# pic_k42.net
KiCad netlist of a schematic drawn in EAGLE
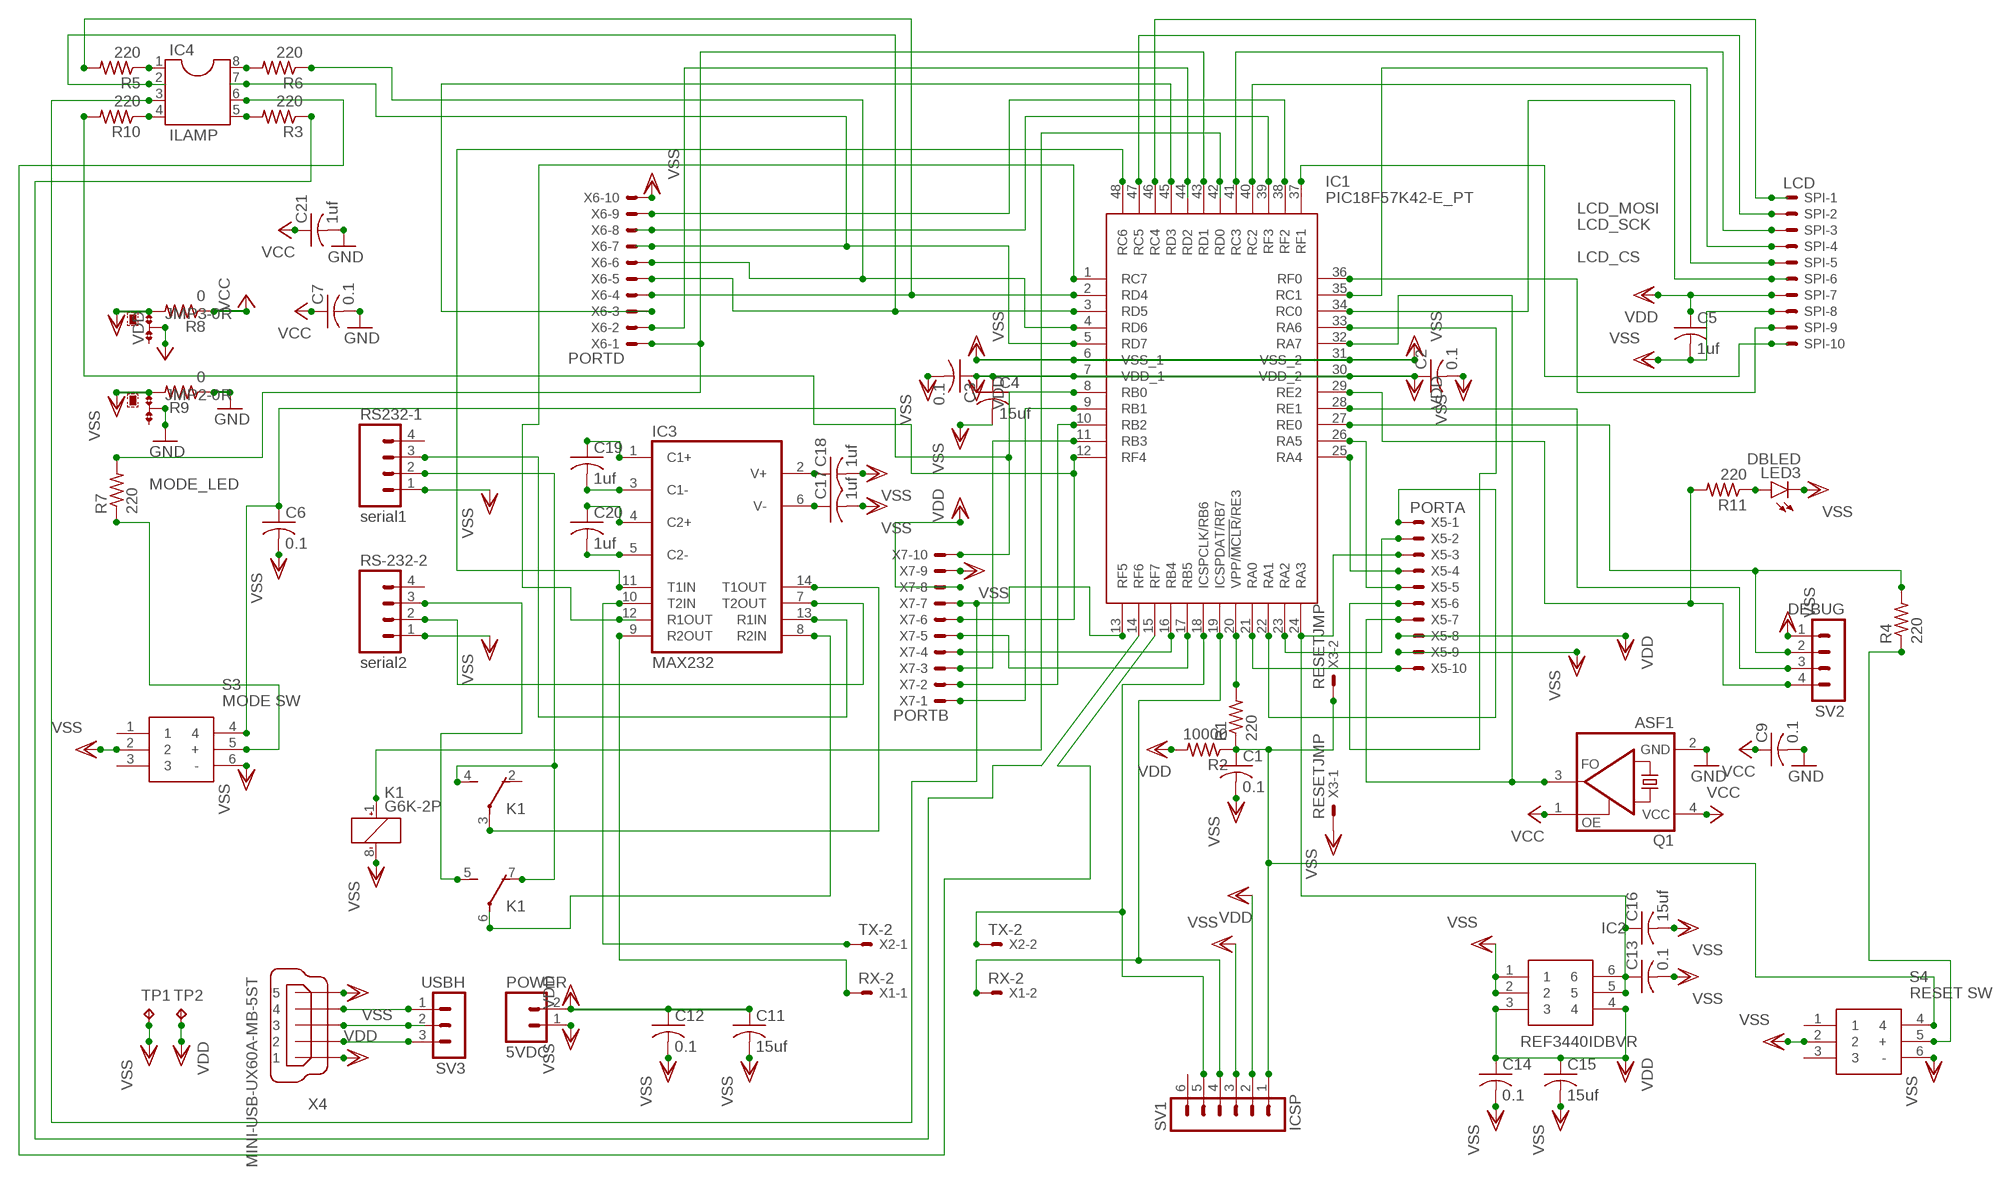
[diagram p0: schematic, sheet 1]

(export (version "E")
  (design (tool "Eeschema 10.0.6"))
  (components
    (comp (ref "C1")
      (value "0.1")
      (footprint "eagle-import:C1206")
      (libsource (lib "eagle-import") (part "C-USC1206"))
    )
    (comp (ref "C2")
      (value "0.1")
      (footprint "eagle-import:C1206")
      (libsource (lib "eagle-import") (part "C-USC1206"))
    )
    (comp (ref "C3")
      (value "0.1")
      (footprint "eagle-import:C1206")
      (libsource (lib "eagle-import") (part "C-USC1206"))
    )
    (comp (ref "C4")
      (value "15uf")
      (footprint "eagle-import:C1206")
      (libsource (lib "eagle-import") (part "C-USC1206"))
    )
    (comp (ref "C5")
      (value "1uf")
      (footprint "eagle-import:C0805")
      (libsource (lib "eagle-import") (part "C-USC0805"))
    )
    (comp (ref "C6")
      (value "0.1")
      (footprint "eagle-import:C1206")
      (libsource (lib "eagle-import") (part "C-USC1206"))
    )
    (comp (ref "C7")
      (value "0.1")
      (footprint "eagle-import:C1206")
      (libsource (lib "eagle-import") (part "C-USC1206"))
    )
    (comp (ref "C9")
      (value "0.1")
      (footprint "eagle-import:C1206")
      (libsource (lib "eagle-import") (part "C-USC1206"))
    )
    (comp (ref "C11")
      (value "15uf")
      (footprint "eagle-import:C1206")
      (libsource (lib "eagle-import") (part "C-USC1206"))
    )
    (comp (ref "C12")
      (value "0.1")
      (footprint "eagle-import:C1206")
      (libsource (lib "eagle-import") (part "C-USC1206"))
    )
    (comp (ref "C13")
      (value "0.1")
      (footprint "eagle-import:C1206")
      (libsource (lib "eagle-import") (part "C-USC1206"))
    )
    (comp (ref "C14")
      (value "0.1")
      (footprint "eagle-import:C1206")
      (libsource (lib "eagle-import") (part "C-USC1206"))
    )
    (comp (ref "C15")
      (value "15uf")
      (footprint "eagle-import:C1206")
      (libsource (lib "eagle-import") (part "C-USC1206"))
    )
    (comp (ref "C16")
      (value "15uf")
      (footprint "eagle-import:C1206")
      (libsource (lib "eagle-import") (part "C-USC1206"))
    )
    (comp (ref "C17")
      (value "1uf")
      (footprint "eagle-import:C0805")
      (libsource (lib "eagle-import") (part "C-USC0805"))
    )
    (comp (ref "C18")
      (value "1uf")
      (footprint "eagle-import:C0805")
      (libsource (lib "eagle-import") (part "C-USC0805"))
    )
    (comp (ref "C19")
      (value "1uf")
      (footprint "eagle-import:C0805")
      (libsource (lib "eagle-import") (part "C-USC0805"))
    )
    (comp (ref "C20")
      (value "1uf")
      (footprint "eagle-import:C0805")
      (libsource (lib "eagle-import") (part "C-USC0805"))
    )
    (comp (ref "C21")
      (value "1uf")
      (footprint "eagle-import:C0805")
      (libsource (lib "eagle-import") (part "C-USC0805"))
    )
    (comp (ref "IC1")
      (value "PIC18F57K42-E_PT")
      (footprint "eagle-import:QFP50P900X900X120-48N")
      (fields
        (field (name "MANUFACTURER_PART_NUMBER") "PIC18F57K42-E/PT")
        (field (name "MOUSER_PART_NUMBER") "579-PIC18F57K42-E/PT")
      )
      (libsource (lib "eagle-import") (part "PIC18F57K42-E_PT"))
    )
    (comp (ref "IC2")
      (value "REF3440IDBVR")
      (footprint "eagle-import:SOP95P280X145-6N")
      (libsource (lib "eagle-import") (part "REF3440IDBVR"))
    )
    (comp (ref "IC3")
      (value "MAX232")
      (footprint "eagle-import:DIL16")
      (fields (field (name "MF") "MAXIM") (field (name "MPN") "MAX232ACPE+"))
      (libsource (lib "eagle-import") (part "MAX232"))
    )
    (comp (ref "IC4")
      (value "ILAMP")
      (footprint "eagle-import:SOCKET-08")
      (libsource (lib "eagle-import") (part "DIL8S"))
    )
    (comp (ref "JMP2")
      (value "0R-JUMPA")
      (footprint "eagle-import:A0R-JMP")
      (libsource (lib "eagle-import") (part "0R-JUMPA"))
    )
    (comp (ref "JMP3")
      (value "0R-JUMPA")
      (footprint "eagle-import:A0R-JMP")
      (libsource (lib "eagle-import") (part "0R-JUMPA"))
    )
    (comp (ref "K1")
      (value "G6K-2P")
      (footprint "eagle-import:G6K-2P")
      (fields (field (name "MF") "OMRON COMPONENTS USA") (field (name "MPN") "G6K-2P DC3"))
      (libsource (lib "eagle-import") (part "G6K-2P"))
    )
    (comp (ref "LED3")
      (value "DBLED")
      (footprint "eagle-import:CHIPLED_1206")
      (libsource (lib "eagle-import") (part "LEDCHIPLED_1206"))
    )
    (comp (ref "POWER")
      (value "5VDC")
      (footprint "eagle-import:02P")
      (libsource (lib "eagle-import") (part "M02"))
    )
    (comp (ref "Q1")
      (value "ASF1")
      (footprint "eagle-import:ASF")
      (libsource (lib "eagle-import") (part "ASF1"))
    )
    (comp (ref "R1")
      (value "220")
      (footprint "eagle-import:R1206")
      (libsource (lib "eagle-import") (part "R-US_R1206"))
    )
    (comp (ref "R2")
      (value "10000")
      (footprint "eagle-import:R1206")
      (libsource (lib "eagle-import") (part "R-US_R1206"))
    )
    (comp (ref "R3")
      (value "220")
      (footprint "eagle-import:R1206")
      (libsource (lib "eagle-import") (part "R-US_R1206"))
    )
    (comp (ref "R4")
      (value "220")
      (footprint "eagle-import:R1206")
      (libsource (lib "eagle-import") (part "R-US_R1206"))
    )
    (comp (ref "R5")
      (value "220")
      (footprint "eagle-import:R1206")
      (libsource (lib "eagle-import") (part "R-US_R1206"))
    )
    (comp (ref "R6")
      (value "220")
      (footprint "eagle-import:R1206")
      (libsource (lib "eagle-import") (part "R-US_R1206"))
    )
    (comp (ref "R7")
      (value "220")
      (footprint "eagle-import:R1206")
      (libsource (lib "eagle-import") (part "R-US_R1206"))
    )
    (comp (ref "R8")
      (value "0")
      (footprint "eagle-import:R1206")
      (libsource (lib "eagle-import") (part "R-US_R1206"))
    )
    (comp (ref "R9")
      (value "0")
      (footprint "eagle-import:R1206")
      (libsource (lib "eagle-import") (part "R-US_R1206"))
    )
    (comp (ref "R10")
      (value "220")
      (footprint "eagle-import:R1206")
      (libsource (lib "eagle-import") (part "R-US_R1206"))
    )
    (comp (ref "R11")
      (value "220")
      (footprint "eagle-import:R1206")
      (libsource (lib "eagle-import") (part "R-US_R1206"))
    )
    (comp (ref "RS-232-2")
      (value "serial2")
      (footprint "eagle-import:04P")
      (libsource (lib "eagle-import") (part "M04"))
    )
    (comp (ref "RS232-1")
      (value "serial1")
      (footprint "eagle-import:04P")
      (libsource (lib "eagle-import") (part "M04"))
    )
    (comp (ref "S3")
      (value "MODE SW")
      (footprint "eagle-import:B3W-9_1-LED")
      (fields
        (field (name "MANUFACTURER_PART_NUMBER") "B3W-9000-Y1N")
        (field (name "MOUSER_PART_NUMBER") "653-B3W-9000-Y1N")
        (field (name "RS_PART_NUMBER") "0492777P")
      )
      (libsource (lib "eagle-import") (part "B3W-9000-Y1N"))
    )
    (comp (ref "S4")
      (value "RESET SW")
      (footprint "eagle-import:B3W-9_1-LED")
      (fields
        (field (name "MANUFACTURER_PART_NUMBER") "B3W-9000-Y1N")
        (field (name "MOUSER_PART_NUMBER") "653-B3W-9000-Y1N")
        (field (name "RS_PART_NUMBER") "0492777P")
      )
      (libsource (lib "eagle-import") (part "B3W-9000-Y1N"))
    )
    (comp (ref "SPI")
      (value "LCD")
      (footprint "eagle-import:22-23-2101")
      (fields (field (name "MF") "MOLEX") (field (name "MPN") "22-23-2101"))
      (libsource (lib "eagle-import") (part "22-23-2101"))
    )
    (comp (ref "SV1")
      (value "ICSP")
      (footprint "eagle-import:MA06-1")
      (libsource (lib "eagle-import") (part "MA06-1"))
    )
    (comp (ref "SV2")
      (value "DEBUG")
      (footprint "eagle-import:MA04-1")
      (libsource (lib "eagle-import") (part "MA04-1"))
    )
    (comp (ref "SV3")
      (value "USBH")
      (footprint "eagle-import:MA03-1")
      (libsource (lib "eagle-import") (part "MA03-1"))
    )
    (comp (ref "TP1")
      (value "TPB1,27")
      (footprint "eagle-import:B1,27")
      (libsource (lib "eagle-import") (part "TPB1,27"))
    )
    (comp (ref "TP2")
      (value "TPB1,27")
      (footprint "eagle-import:B1,27")
      (libsource (lib "eagle-import") (part "TPB1,27"))
    )
    (comp (ref "X1")
      (value "RX-2")
      (footprint "eagle-import:332-02")
      (libsource (lib "eagle-import") (part "332-02"))
    )
    (comp (ref "X2")
      (value "TX-2")
      (footprint "eagle-import:332-02")
      (libsource (lib "eagle-import") (part "332-02"))
    )
    (comp (ref "X3")
      (value "RESETJMP")
      (footprint "eagle-import:332-02")
      (libsource (lib "eagle-import") (part "332-02"))
    )
    (comp (ref "X4")
      (value "MINI-USB-UX60A-MB-5ST")
      (footprint "eagle-import:UX60A-MB-5ST")
      (libsource (lib "eagle-import") (part "MINI-USB-UX60A-MB-5ST"))
    )
    (comp (ref "X5")
      (value "PORTA")
      (footprint "eagle-import:22-23-2101")
      (fields (field (name "MF") "MOLEX") (field (name "MPN") "22-23-2101"))
      (libsource (lib "eagle-import") (part "22-23-2101"))
    )
    (comp (ref "X6")
      (value "PORTD")
      (footprint "eagle-import:22-23-2101")
      (fields (field (name "MF") "MOLEX") (field (name "MPN") "22-23-2101"))
      (libsource (lib "eagle-import") (part "22-23-2101"))
    )
    (comp (ref "X7")
      (value "PORTB")
      (footprint "eagle-import:22-23-2101")
      (fields (field (name "MF") "MOLEX") (field (name "MPN") "22-23-2101"))
      (libsource (lib "eagle-import") (part "22-23-2101"))
    )
  )
  (nets
    (net (code "1") (name "/LCD_CS") (class "Default")
      (node (ref "IC1") (pin "40") (pinfunction "RC2_40") (pintype "bidirectional"))
      (node (ref "SPI") (pin "5") (pinfunction "S_5") (pintype "passive"))
    )
    (net (code "2") (name "/LCD_MOSI") (class "Default")
      (node (ref "IC1") (pin "47") (pinfunction "RC5_47") (pintype "bidirectional"))
      (node (ref "SPI") (pin "2") (pinfunction "S_2") (pintype "passive"))
    )
    (net (code "3") (name "/LCD_SCK") (class "Default")
      (node (ref "IC1") (pin "41") (pinfunction "RC3_41") (pintype "bidirectional"))
      (node (ref "SPI") (pin "3") (pinfunction "S_3") (pintype "passive"))
    )
    (net (code "4") (name "/MODE_LED") (class "Default")
      (node (ref "IC1") (pin "43") (pinfunction "RD1_43") (pintype "bidirectional"))
      (node (ref "R7") (pin "2") (pinfunction "2_2") (pintype "passive"))
      (node (ref "X6") (pin "1") (pinfunction "S_1") (pintype "passive"))
    )
    (net (code "5") (name "GND") (class "Default")
      (node (ref "C21") (pin "2") (pinfunction "2_2") (pintype "passive"))
      (node (ref "C7") (pin "2") (pinfunction "2_2") (pintype "passive"))
      (node (ref "C9") (pin "2") (pinfunction "2_2") (pintype "passive"))
      (node (ref "JMP2") (pin "2") (pinfunction "2_2") (pintype "passive"))
      (node (ref "Q1") (pin "2") (pinfunction "GND_2") (pintype "power_in"))
      (node (ref "R9") (pin "1") (pinfunction "1_1") (pintype "passive"))
    )
    (net (code "6") (name "Net-(IC1-ICSPCLK{slash}RB6)") (class "Default")
      (node (ref "IC1") (pin "18") (pinfunction "ICSPCLK/RB6_18") (pintype "bidirectional"))
      (node (ref "SV1") (pin "5") (pinfunction "5_5") (pintype "passive"))
      (node (ref "X2") (pin "2") (pinfunction "S_2") (pintype "passive"))
    )
    (net (code "7") (name "Net-(IC1-ICSPDAT{slash}RB7)") (class "Default")
      (node (ref "IC1") (pin "19") (pinfunction "ICSPDAT/RB7_19") (pintype "bidirectional"))
      (node (ref "SV1") (pin "4") (pinfunction "4_4") (pintype "passive"))
      (node (ref "X1") (pin "2") (pinfunction "S_2") (pintype "passive"))
    )
    (net (code "8") (name "Net-(IC1-RA0)") (class "Default")
      (node (ref "IC1") (pin "21") (pinfunction "RA0_21") (pintype "bidirectional"))
      (node (ref "X5") (pin "10") (pinfunction "S_10") (pintype "passive"))
    )
    (net (code "9") (name "Net-(IC1-RA1)") (class "Default")
      (node (ref "IC1") (pin "22") (pinfunction "RA1_22") (pintype "bidirectional"))
      (node (ref "X5") (pin "1") (pinfunction "S_1") (pintype "passive"))
    )
    (net (code "10") (name "Net-(IC1-RA2)") (class "Default")
      (node (ref "IC1") (pin "23") (pinfunction "RA2_23") (pintype "bidirectional"))
      (node (ref "X5") (pin "2") (pinfunction "S_2") (pintype "passive"))
    )
    (net (code "11") (name "Net-(IC1-RA3)") (class "Default")
      (node (ref "C13") (pin "1") (pinfunction "1_1") (pintype "passive"))
      (node (ref "C16") (pin "1") (pinfunction "1_1") (pintype "passive"))
      (node (ref "IC1") (pin "24") (pinfunction "RA3_24") (pintype "bidirectional"))
      (node (ref "IC2") (pin "5") (pinfunction "5_5") (pintype "bidirectional"))
      (node (ref "IC2") (pin "6") (pinfunction "6_6") (pintype "bidirectional"))
      (node (ref "X5") (pin "3") (pinfunction "S_3") (pintype "passive"))
    )
    (net (code "12") (name "Net-(IC1-RA4)") (class "Default")
      (node (ref "IC1") (pin "25") (pinfunction "RA4_25") (pintype "bidirectional"))
      (node (ref "X5") (pin "4") (pinfunction "S_4") (pintype "passive"))
    )
    (net (code "13") (name "Net-(IC1-RA5)") (class "Default")
      (node (ref "IC1") (pin "26") (pinfunction "RA5_26") (pintype "bidirectional"))
      (node (ref "X5") (pin "5") (pinfunction "S_5") (pintype "passive"))
    )
    (net (code "14") (name "Net-(IC1-RA6)") (class "Default")
      (node (ref "IC1") (pin "33") (pinfunction "RA6_33") (pintype "bidirectional"))
      (node (ref "X5") (pin "6") (pinfunction "S_6") (pintype "passive"))
    )
    (net (code "15") (name "Net-(IC1-RA7)") (class "Default")
      (node (ref "IC1") (pin "32") (pinfunction "RA7_32") (pintype "bidirectional"))
      (node (ref "Q1") (pin "3") (pinfunction "FO_3") (pintype "output"))
      (node (ref "X5") (pin "7") (pinfunction "S_7") (pintype "passive"))
    )
    (net (code "16") (name "Net-(IC1-RB0)") (class "Default")
      (node (ref "C6") (pin "1") (pinfunction "1_1") (pintype "passive"))
      (node (ref "IC1") (pin "8") (pinfunction "RB0_8") (pintype "bidirectional"))
      (node (ref "S3") (pin "4") (pinfunction "4_4") (pintype "bidirectional"))
      (node (ref "X7") (pin "10") (pinfunction "S_10") (pintype "passive"))
    )
    (net (code "17") (name "Net-(IC1-RB1)") (class "Default")
      (node (ref "IC1") (pin "9") (pinfunction "RB1_9") (pintype "bidirectional"))
      (node (ref "X7") (pin "1") (pinfunction "S_1") (pintype "passive"))
    )
    (net (code "18") (name "Net-(IC1-RB2)") (class "Default")
      (node (ref "IC1") (pin "10") (pinfunction "RB2_10") (pintype "bidirectional"))
      (node (ref "X7") (pin "2") (pinfunction "S_2") (pintype "passive"))
    )
    (net (code "19") (name "Net-(IC1-RB3)") (class "Default")
      (node (ref "IC1") (pin "11") (pinfunction "RB3_11") (pintype "bidirectional"))
      (node (ref "X7") (pin "3") (pinfunction "S_3") (pintype "passive"))
    )
    (net (code "20") (name "Net-(IC1-RB4)") (class "Default")
      (node (ref "IC1") (pin "16") (pinfunction "RB4_16") (pintype "bidirectional"))
      (node (ref "X7") (pin "4") (pinfunction "S_4") (pintype "passive"))
    )
    (net (code "21") (name "Net-(IC1-RB5)") (class "Default")
      (node (ref "IC1") (pin "17") (pinfunction "RB5_17") (pintype "bidirectional"))
      (node (ref "X7") (pin "5") (pinfunction "S_5") (pintype "passive"))
    )
    (net (code "22") (name "Net-(IC1-RC0)") (class "Default")
      (node (ref "IC1") (pin "34") (pinfunction "RC0_34") (pintype "bidirectional"))
      (node (ref "SPI") (pin "6") (pinfunction "S_6") (pintype "passive"))
    )
    (net (code "23") (name "Net-(IC1-RC1)") (class "Default")
      (node (ref "IC1") (pin "35") (pinfunction "RC1_35") (pintype "bidirectional"))
      (node (ref "SPI") (pin "4") (pinfunction "S_4") (pintype "passive"))
    )
    (net (code "24") (name "Net-(IC1-RC4)") (class "Default")
      (node (ref "IC1") (pin "46") (pinfunction "RC4_46") (pintype "bidirectional"))
      (node (ref "SPI") (pin "1") (pinfunction "S_1") (pintype "passive"))
    )
    (net (code "25") (name "Net-(IC1-RC6)") (class "Default")
      (node (ref "IC1") (pin "48") (pinfunction "RC6_48") (pintype "bidirectional"))
      (node (ref "IC3") (pin "11") (pinfunction "T1IN_11") (pintype "input"))
    )
    (net (code "26") (name "Net-(IC1-RC7)") (class "Default")
      (node (ref "IC1") (pin "1") (pinfunction "RC7_1") (pintype "bidirectional"))
      (node (ref "IC3") (pin "12") (pinfunction "R1OUT_12") (pintype "output"))
    )
    (net (code "27") (name "Net-(IC1-RD0)") (class "Default")
      (node (ref "IC1") (pin "42") (pinfunction "RD0_42") (pintype "bidirectional"))
      (node (ref "K1") (pin "1") (pinfunction "+_1") (pintype "passive"))
    )
    (net (code "28") (name "Net-(IC1-RD2)") (class "Default")
      (node (ref "IC1") (pin "44") (pinfunction "RD2_44") (pintype "bidirectional"))
      (node (ref "X6") (pin "2") (pinfunction "S_2") (pintype "passive"))
    )
    (net (code "29") (name "Net-(IC1-RD3)") (class "Default")
      (node (ref "IC1") (pin "45") (pinfunction "RD3_45") (pintype "bidirectional"))
      (node (ref "X6") (pin "3") (pinfunction "S_3") (pintype "passive"))
    )
    (net (code "30") (name "Net-(IC1-RD4)") (class "Default")
      (node (ref "IC1") (pin "2") (pinfunction "RD4_2") (pintype "bidirectional"))
      (node (ref "R5") (pin "2") (pinfunction "2_2") (pintype "passive"))
      (node (ref "X6") (pin "4") (pinfunction "S_4") (pintype "passive"))
    )
    (net (code "31") (name "Net-(IC1-RD5)") (class "Default")
      (node (ref "IC1") (pin "3") (pinfunction "RD5_3") (pintype "bidirectional"))
      (node (ref "IC4") (pin "2") (pinfunction "2_2") (pintype "passive"))
      (node (ref "X6") (pin "5") (pinfunction "S_5") (pintype "passive"))
    )
    (net (code "32") (name "Net-(IC1-RD6)") (class "Default")
      (node (ref "IC1") (pin "4") (pinfunction "RD6_4") (pintype "bidirectional"))
      (node (ref "R6") (pin "1") (pinfunction "1_1") (pintype "passive"))
      (node (ref "X6") (pin "6") (pinfunction "S_6") (pintype "passive"))
    )
    (net (code "33") (name "Net-(IC1-RD7)") (class "Default")
      (node (ref "IC1") (pin "5") (pinfunction "RD7_5") (pintype "bidirectional"))
      (node (ref "IC4") (pin "7") (pinfunction "7_7") (pintype "passive"))
      (node (ref "X6") (pin "7") (pinfunction "S_7") (pintype "passive"))
    )
    (net (code "34") (name "Net-(IC1-RE0)") (class "Default")
      (node (ref "IC1") (pin "27") (pinfunction "RE0_27") (pintype "bidirectional"))
      (node (ref "R4") (pin "2") (pinfunction "2_2") (pintype "passive"))
      (node (ref "SV2") (pin "2") (pinfunction "2_2") (pintype "passive"))
    )
    (net (code "35") (name "Net-(IC1-RE1)") (class "Default")
      (node (ref "IC1") (pin "28") (pinfunction "RE1_28") (pintype "bidirectional"))
      (node (ref "SV2") (pin "3") (pinfunction "3_3") (pintype "passive"))
    )
    (net (code "36") (name "Net-(IC1-RE2)") (class "Default")
      (node (ref "IC1") (pin "29") (pinfunction "RE2_29") (pintype "bidirectional"))
      (node (ref "R11") (pin "2") (pinfunction "2_2") (pintype "passive"))
      (node (ref "SV2") (pin "4") (pinfunction "4_4") (pintype "passive"))
    )
    (net (code "37") (name "Net-(IC1-RF0)") (class "Default")
      (node (ref "IC1") (pin "36") (pinfunction "RF0_36") (pintype "bidirectional"))
      (node (ref "SPI") (pin "9") (pinfunction "S_9") (pintype "passive"))
    )
    (net (code "38") (name "Net-(IC1-RF1)") (class "Default")
      (node (ref "IC1") (pin "37") (pinfunction "RF1_37") (pintype "bidirectional"))
      (node (ref "SPI") (pin "10") (pinfunction "S_10") (pintype "passive"))
    )
    (net (code "39") (name "Net-(IC1-RF2)") (class "Default")
      (node (ref "IC1") (pin "38") (pinfunction "RF2_38") (pintype "bidirectional"))
      (node (ref "X6") (pin "9") (pinfunction "S_9") (pintype "passive"))
    )
    (net (code "40") (name "Net-(IC1-RF3)") (class "Default")
      (node (ref "IC1") (pin "39") (pinfunction "RF3_39") (pintype "bidirectional"))
      (node (ref "X6") (pin "8") (pinfunction "S_8") (pintype "passive"))
    )
    (net (code "41") (name "Net-(IC1-RF4)") (class "Default")
      (node (ref "IC1") (pin "12") (pinfunction "RF4_12") (pintype "bidirectional"))
      (node (ref "R10") (pin "2") (pinfunction "2_2") (pintype "passive"))
      (node (ref "X7") (pin "6") (pinfunction "S_6") (pintype "passive"))
    )
    (net (code "42") (name "Net-(IC1-RF5)") (class "Default")
      (node (ref "IC1") (pin "13") (pinfunction "RF5_13") (pintype "bidirectional"))
      (node (ref "IC4") (pin "3") (pinfunction "3_3") (pintype "passive"))
      (node (ref "X7") (pin "7") (pinfunction "S_7") (pintype "passive"))
    )
    (net (code "43") (name "Net-(IC1-RF6)") (class "Default")
      (node (ref "IC1") (pin "14") (pinfunction "RF6_14") (pintype "bidirectional"))
      (node (ref "R3") (pin "1") (pinfunction "1_1") (pintype "passive"))
    )
    (net (code "44") (name "Net-(IC1-RF7)") (class "Default")
      (node (ref "IC1") (pin "15") (pinfunction "RF7_15") (pintype "bidirectional"))
      (node (ref "IC4") (pin "6") (pinfunction "6_6") (pintype "passive"))
    )
    (net (code "45") (name "Net-(IC1-VPP{slash}~{MCLR}{slash}RE3)") (class "Default")
      (node (ref "IC1") (pin "20") (pinfunction "VPP/~{MCLR}/RE3_20") (pintype "bidirectional"))
      (node (ref "R1") (pin "2") (pinfunction "2_2") (pintype "passive"))
    )
    (net (code "46") (name "Net-(IC3A-C1+)") (class "Default")
      (node (ref "C19") (pin "1") (pinfunction "1_1") (pintype "passive"))
      (node (ref "IC3") (pin "1") (pinfunction "C1+_1") (pintype "bidirectional"))
    )
    (net (code "47") (name "Net-(IC3A-C1-)") (class "Default")
      (node (ref "C19") (pin "2") (pinfunction "2_2") (pintype "passive"))
      (node (ref "IC3") (pin "3") (pinfunction "C1-_3") (pintype "bidirectional"))
    )
    (net (code "48") (name "Net-(IC3A-C2+)") (class "Default")
      (node (ref "C20") (pin "1") (pinfunction "1_1") (pintype "passive"))
      (node (ref "IC3") (pin "4") (pinfunction "C2+_4") (pintype "bidirectional"))
    )
    (net (code "49") (name "Net-(IC3A-C2-)") (class "Default")
      (node (ref "C20") (pin "2") (pinfunction "2_2") (pintype "passive"))
      (node (ref "IC3") (pin "5") (pinfunction "C2-_5") (pintype "bidirectional"))
    )
    (net (code "50") (name "Net-(IC3A-R1IN)") (class "Default")
      (node (ref "IC3") (pin "13") (pinfunction "R1IN_13") (pintype "input"))
      (node (ref "RS232-1") (pin "3") (pinfunction "3_3") (pintype "passive"))
    )
    (net (code "51") (name "Net-(IC3A-R2IN)") (class "Default")
      (node (ref "IC3") (pin "8") (pinfunction "R2IN_8") (pintype "input"))
      (node (ref "K1") (pin "6") (pinfunction "P_6") (pintype "passive"))
    )
    (net (code "52") (name "Net-(IC3A-R2OUT)") (class "Default")
      (node (ref "IC3") (pin "9") (pinfunction "R2OUT_9") (pintype "output"))
      (node (ref "X1") (pin "1") (pinfunction "S_1") (pintype "passive"))
    )
    (net (code "53") (name "Net-(IC3A-T1OUT)") (class "Default")
      (node (ref "IC3") (pin "14") (pinfunction "T1OUT_14") (pintype "output"))
      (node (ref "K1") (pin "3") (pinfunction "P_3") (pintype "passive"))
    )
    (net (code "54") (name "Net-(IC3A-T2IN)") (class "Default")
      (node (ref "IC3") (pin "10") (pinfunction "T2IN_10") (pintype "input"))
      (node (ref "X2") (pin "1") (pinfunction "S_1") (pintype "passive"))
    )
    (net (code "55") (name "Net-(IC3A-T2OUT)") (class "Default")
      (node (ref "IC3") (pin "7") (pinfunction "T2OUT_7") (pintype "output"))
      (node (ref "RS-232-2") (pin "2") (pinfunction "2_2") (pintype "passive"))
    )
    (net (code "56") (name "Net-(IC3A-V+)") (class "Default")
      (node (ref "C18") (pin "1") (pinfunction "1_1") (pintype "passive"))
      (node (ref "IC3") (pin "2") (pinfunction "V+_2") (pintype "bidirectional"))
    )
    (net (code "57") (name "Net-(IC3A-V-)") (class "Default")
      (node (ref "C17") (pin "1") (pinfunction "1_1") (pintype "passive"))
      (node (ref "IC3") (pin "6") (pinfunction "V-_6") (pintype "bidirectional"))
    )
    (net (code "58") (name "Net-(IC4-Pad1)") (class "Default")
      (node (ref "IC4") (pin "1") (pinfunction "1_1") (pintype "passive"))
      (node (ref "R5") (pin "1") (pinfunction "1_1") (pintype "passive"))
    )
    (net (code "59") (name "Net-(IC4-Pad4)") (class "Default")
      (node (ref "IC4") (pin "4") (pinfunction "4_4") (pintype "passive"))
      (node (ref "R10") (pin "1") (pinfunction "1_1") (pintype "passive"))
    )
    (net (code "60") (name "Net-(IC4-Pad5)") (class "Default")
      (node (ref "IC4") (pin "5") (pinfunction "5_5") (pintype "passive"))
      (node (ref "R3") (pin "2") (pinfunction "2_2") (pintype "passive"))
    )
    (net (code "61") (name "Net-(IC4-Pad8)") (class "Default")
      (node (ref "IC4") (pin "8") (pinfunction "8_8") (pintype "passive"))
      (node (ref "R6") (pin "2") (pinfunction "2_2") (pintype "passive"))
    )
    (net (code "62") (name "Net-(K1B-S)") (class "Default")
      (node (ref "K1") (pin "4") (pinfunction "S_4") (pintype "passive"))
      (node (ref "K1") (pin "7") (pinfunction "O_7") (pintype "passive"))
      (node (ref "RS232-1") (pin "2") (pinfunction "2_2") (pintype "passive"))
    )
    (net (code "63") (name "Net-(K1C-S)") (class "Default")
      (node (ref "K1") (pin "5") (pinfunction "S_5") (pintype "passive"))
      (node (ref "RS-232-2") (pin "3") (pinfunction "3_3") (pintype "passive"))
    )
    (net (code "64") (name "Net-(LED3-PadA)") (class "Default")
      (node (ref "LED3") (pin "A") (pinfunction "A_A") (pintype "passive"))
      (node (ref "R11") (pin "1") (pinfunction "1_1") (pintype "passive"))
    )
    (net (code "65") (name "Net-(S3-+)") (class "Default")
      (node (ref "R7") (pin "1") (pinfunction "1_1") (pintype "passive"))
      (node (ref "S3") (pin "5") (pinfunction "+_5") (pintype "bidirectional"))
    )
    (net (code "66") (name "Net-(S4-+)") (class "Default")
      (node (ref "R4") (pin "1") (pinfunction "1_1") (pintype "passive"))
      (node (ref "S4") (pin "5") (pinfunction "+_5") (pintype "bidirectional"))
    )
    (net (code "67") (name "Net-(SV3-Pad1)") (class "Default")
      (node (ref "SV3") (pin "1") (pinfunction "1_1") (pintype "passive"))
      (node (ref "X4") (pin "4") (pinfunction "4_4") (pintype "input"))
    )
    (net (code "68") (name "Net-(SV3-Pad2)") (class "Default")
      (node (ref "SV3") (pin "2") (pinfunction "2_2") (pintype "passive"))
      (node (ref "X4") (pin "3") (pinfunction "3_3") (pintype "input"))
    )
    (net (code "69") (name "Net-(SV3-Pad3)") (class "Default")
      (node (ref "SV3") (pin "3") (pinfunction "3_3") (pintype "passive"))
      (node (ref "X4") (pin "2") (pinfunction "2_2") (pintype "input"))
    )
    (net (code "70") (name "Net-(X3B-S)") (class "Default")
      (node (ref "C1") (pin "1") (pinfunction "1_1") (pintype "passive"))
      (node (ref "R1") (pin "1") (pinfunction "1_1") (pintype "passive"))
      (node (ref "R2") (pin "1") (pinfunction "1_1") (pintype "passive"))
      (node (ref "S4") (pin "4") (pinfunction "4_4") (pintype "bidirectional"))
      (node (ref "SV1") (pin "1") (pinfunction "1_1") (pintype "passive"))
      (node (ref "X3") (pin "2") (pinfunction "S_2") (pintype "passive"))
    )
    (net (code "71") (name "VCC") (class "Default")
      (node (ref "C21") (pin "1") (pinfunction "1_1") (pintype "passive"))
      (node (ref "C7") (pin "1") (pinfunction "1_1") (pintype "passive"))
      (node (ref "C9") (pin "1") (pinfunction "1_1") (pintype "passive"))
      (node (ref "JMP3") (pin "2") (pinfunction "2_2") (pintype "passive"))
      (node (ref "Q1") (pin "1") (pinfunction "OE_1") (pintype "input"))
      (node (ref "Q1") (pin "4") (pinfunction "VCC_4") (pintype "power_in"))
      (node (ref "R8") (pin "1") (pinfunction "1_1") (pintype "passive"))
    )
    (net (code "72") (name "VDD") (class "Default")
      (node (ref "C11") (pin "1") (pinfunction "1_1") (pintype "passive"))
      (node (ref "C12") (pin "1") (pinfunction "1_1") (pintype "passive"))
      (node (ref "C14") (pin "1") (pinfunction "1_1") (pintype "passive"))
      (node (ref "C15") (pin "1") (pinfunction "1_1") (pintype "passive"))
      (node (ref "C2") (pin "1") (pinfunction "1_1") (pintype "passive"))
      (node (ref "C3") (pin "1") (pinfunction "1_1") (pintype "passive"))
      (node (ref "C4") (pin "1") (pinfunction "1_1") (pintype "passive"))
      (node (ref "C5") (pin "1") (pinfunction "1_1") (pintype "passive"))
      (node (ref "IC1") (pin "30") (pinfunction "VDD_2_30") (pintype "bidirectional"))
      (node (ref "IC1") (pin "7") (pinfunction "VDD_1_7") (pintype "bidirectional"))
      (node (ref "IC2") (pin "3") (pinfunction "3_3") (pintype "bidirectional"))
      (node (ref "IC2") (pin "4") (pinfunction "4_4") (pintype "bidirectional"))
      (node (ref "JMP3") (pin "1") (pinfunction "1_1") (pintype "passive"))
      (node (ref "POWER") (pin "2") (pinfunction "2_2") (pintype "passive"))
      (node (ref "R2") (pin "2") (pinfunction "2_2") (pintype "passive"))
      (node (ref "R8") (pin "2") (pinfunction "2_2") (pintype "passive"))
      (node (ref "SPI") (pin "7") (pinfunction "S_7") (pintype "passive"))
      (node (ref "SV1") (pin "2") (pinfunction "2_2") (pintype "passive"))
      (node (ref "TP2") (pin "TP") (pinfunction "TP_TP") (pintype "input"))
      (node (ref "X4") (pin "1") (pinfunction "1_1") (pintype "input"))
      (node (ref "X5") (pin "8") (pinfunction "S_8") (pintype "passive"))
      (node (ref "X7") (pin "8") (pinfunction "S_8") (pintype "passive"))
    )
    (net (code "73") (name "VSS") (class "Default")
      (node (ref "C1") (pin "2") (pinfunction "2_2") (pintype "passive"))
      (node (ref "C11") (pin "2") (pinfunction "2_2") (pintype "passive"))
      (node (ref "C12") (pin "2") (pinfunction "2_2") (pintype "passive"))
      (node (ref "C13") (pin "2") (pinfunction "2_2") (pintype "passive"))
      (node (ref "C14") (pin "2") (pinfunction "2_2") (pintype "passive"))
      (node (ref "C15") (pin "2") (pinfunction "2_2") (pintype "passive"))
      (node (ref "C16") (pin "2") (pinfunction "2_2") (pintype "passive"))
      (node (ref "C17") (pin "2") (pinfunction "2_2") (pintype "passive"))
      (node (ref "C18") (pin "2") (pinfunction "2_2") (pintype "passive"))
      (node (ref "C2") (pin "2") (pinfunction "2_2") (pintype "passive"))
      (node (ref "C3") (pin "2") (pinfunction "2_2") (pintype "passive"))
      (node (ref "C4") (pin "2") (pinfunction "2_2") (pintype "passive"))
      (node (ref "C5") (pin "2") (pinfunction "2_2") (pintype "passive"))
      (node (ref "C6") (pin "2") (pinfunction "2_2") (pintype "passive"))
      (node (ref "IC1") (pin "31") (pinfunction "VSS_2_31") (pintype "bidirectional"))
      (node (ref "IC1") (pin "6") (pinfunction "VSS_1_6") (pintype "bidirectional"))
      (node (ref "IC2") (pin "1") (pinfunction "1_1") (pintype "bidirectional"))
      (node (ref "IC2") (pin "2") (pinfunction "2_2") (pintype "bidirectional"))
      (node (ref "JMP2") (pin "1") (pinfunction "1_1") (pintype "passive"))
      (node (ref "K1") (pin "8") (pinfunction "-_8") (pintype "passive"))
      (node (ref "LED3") (pin "C") (pinfunction "C_C") (pintype "passive"))
      (node (ref "POWER") (pin "1") (pinfunction "1_1") (pintype "passive"))
      (node (ref "R9") (pin "2") (pinfunction "2_2") (pintype "passive"))
      (node (ref "RS-232-2") (pin "1") (pinfunction "1_1") (pintype "passive"))
      (node (ref "RS232-1") (pin "1") (pinfunction "1_1") (pintype "passive"))
      (node (ref "S3") (pin "2") (pinfunction "2_2") (pintype "bidirectional"))
      (node (ref "S3") (pin "6") (pinfunction "-_6") (pintype "bidirectional"))
      (node (ref "S4") (pin "2") (pinfunction "2_2") (pintype "bidirectional"))
      (node (ref "S4") (pin "6") (pinfunction "-_6") (pintype "bidirectional"))
      (node (ref "SPI") (pin "8") (pinfunction "S_8") (pintype "passive"))
      (node (ref "SV1") (pin "3") (pinfunction "3_3") (pintype "passive"))
      (node (ref "SV2") (pin "1") (pinfunction "1_1") (pintype "passive"))
      (node (ref "TP1") (pin "TP") (pinfunction "TP_TP") (pintype "input"))
      (node (ref "X3") (pin "1") (pinfunction "S_1") (pintype "passive"))
      (node (ref "X4") (pin "5") (pinfunction "5_5") (pintype "input"))
      (node (ref "X5") (pin "9") (pinfunction "S_9") (pintype "passive"))
      (node (ref "X6") (pin "10") (pinfunction "S_10") (pintype "passive"))
      (node (ref "X7") (pin "9") (pinfunction "S_9") (pintype "passive"))
    )
    (net (code "74") (name "unconnected-(JMP2-Pad3)") (class "Default")
      (node (ref "JMP2") (pin "3") (pinfunction "3_3") (pintype "passive"))
    )
    (net (code "75") (name "unconnected-(JMP3-Pad3)") (class "Default")
      (node (ref "JMP3") (pin "3") (pinfunction "3_3") (pintype "passive"))
    )
    (net (code "76") (name "unconnected-(K1B-O-Pad2)") (class "Default")
      (node (ref "K1") (pin "2") (pinfunction "O_2") (pintype "passive"))
    )
    (net (code "77") (name "unconnected-(RS-232-2-Pad4)") (class "Default")
      (node (ref "RS-232-2") (pin "4") (pinfunction "4_4") (pintype "passive"))
    )
    (net (code "78") (name "unconnected-(RS232-1-Pad4)") (class "Default")
      (node (ref "RS232-1") (pin "4") (pinfunction "4_4") (pintype "passive"))
    )
    (net (code "79") (name "unconnected-(S3-Pad1)") (class "Default")
      (node (ref "S3") (pin "1") (pinfunction "1_1") (pintype "bidirectional"))
    )
    (net (code "80") (name "unconnected-(S3-Pad3)") (class "Default")
      (node (ref "S3") (pin "3") (pinfunction "3_3") (pintype "bidirectional"))
    )
    (net (code "81") (name "unconnected-(S4-Pad1)") (class "Default")
      (node (ref "S4") (pin "1") (pinfunction "1_1") (pintype "bidirectional"))
    )
    (net (code "82") (name "unconnected-(S4-Pad3)") (class "Default")
      (node (ref "S4") (pin "3") (pinfunction "3_3") (pintype "bidirectional"))
    )
    (net (code "83") (name "unconnected-(SV1-Pad6)") (class "Default")
      (node (ref "SV1") (pin "6") (pinfunction "6_6") (pintype "passive"))
    )
  )
)
